# steering_engine_interface.net
KiCad netlist of a schematic drawn in Altium Designer
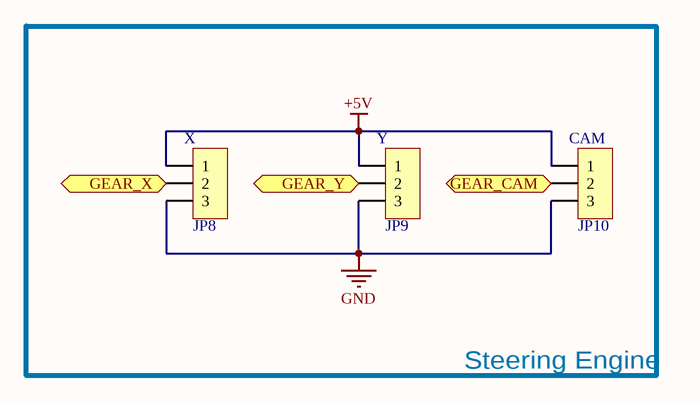
[diagram p0: steering_engine_interface.SchDoc]

(export (version "E")
  (design (tool "Eeschema 10.0.6"))
  (components
    (comp (ref "JP8")
      (value "X")
      (footprint "HDR2.54-LI-3P")
      (description "3P接插件")
      (fields (field (name "版权归属") "源创客"))
      (libsource (lib "4.5   - 接插件-脚距2.54") (part "Header 3"))
    )
    (comp (ref "JP9")
      (value "Y")
      (footprint "HDR2.54-LI-3P")
      (description "3P接插件")
      (fields (field (name "版权归属") "源创客"))
      (libsource (lib "4.5   - 接插件-脚距2.54") (part "Header 3"))
    )
    (comp (ref "JP10")
      (value "CAM")
      (footprint "HDR2.54-LI-3P")
      (description "3P接插件")
      (fields (field (name "版权归属") "源创客"))
      (libsource (lib "4.5   - 接插件-脚距2.54") (part "Header 3"))
    )
  )
  (nets
    (net (code "1") (name "+5V") (class "Default")
      (node (ref "JP10") (pin "1") (pinfunction "1_1") (pintype "passive"))
      (node (ref "JP8") (pin "1") (pinfunction "1_1") (pintype "passive"))
      (node (ref "JP9") (pin "1") (pinfunction "1_1") (pintype "passive"))
    )
    (net (code "2") (name "/GEAR_CAM") (class "Default")
      (node (ref "JP10") (pin "2") (pinfunction "2_2") (pintype "passive"))
    )
    (net (code "3") (name "/GEAR_X") (class "Default")
      (node (ref "JP8") (pin "2") (pinfunction "2_2") (pintype "passive"))
    )
    (net (code "4") (name "/GEAR_Y") (class "Default")
      (node (ref "JP9") (pin "2") (pinfunction "2_2") (pintype "passive"))
    )
    (net (code "5") (name "GND") (class "Default")
      (node (ref "JP10") (pin "3") (pinfunction "3_3") (pintype "passive"))
      (node (ref "JP8") (pin "3") (pinfunction "3_3") (pintype "passive"))
      (node (ref "JP9") (pin "3") (pinfunction "3_3") (pintype "passive"))
    )
  )
)
